# Schemtatic.net
KiCad netlist of a schematic drawn in EAGLE
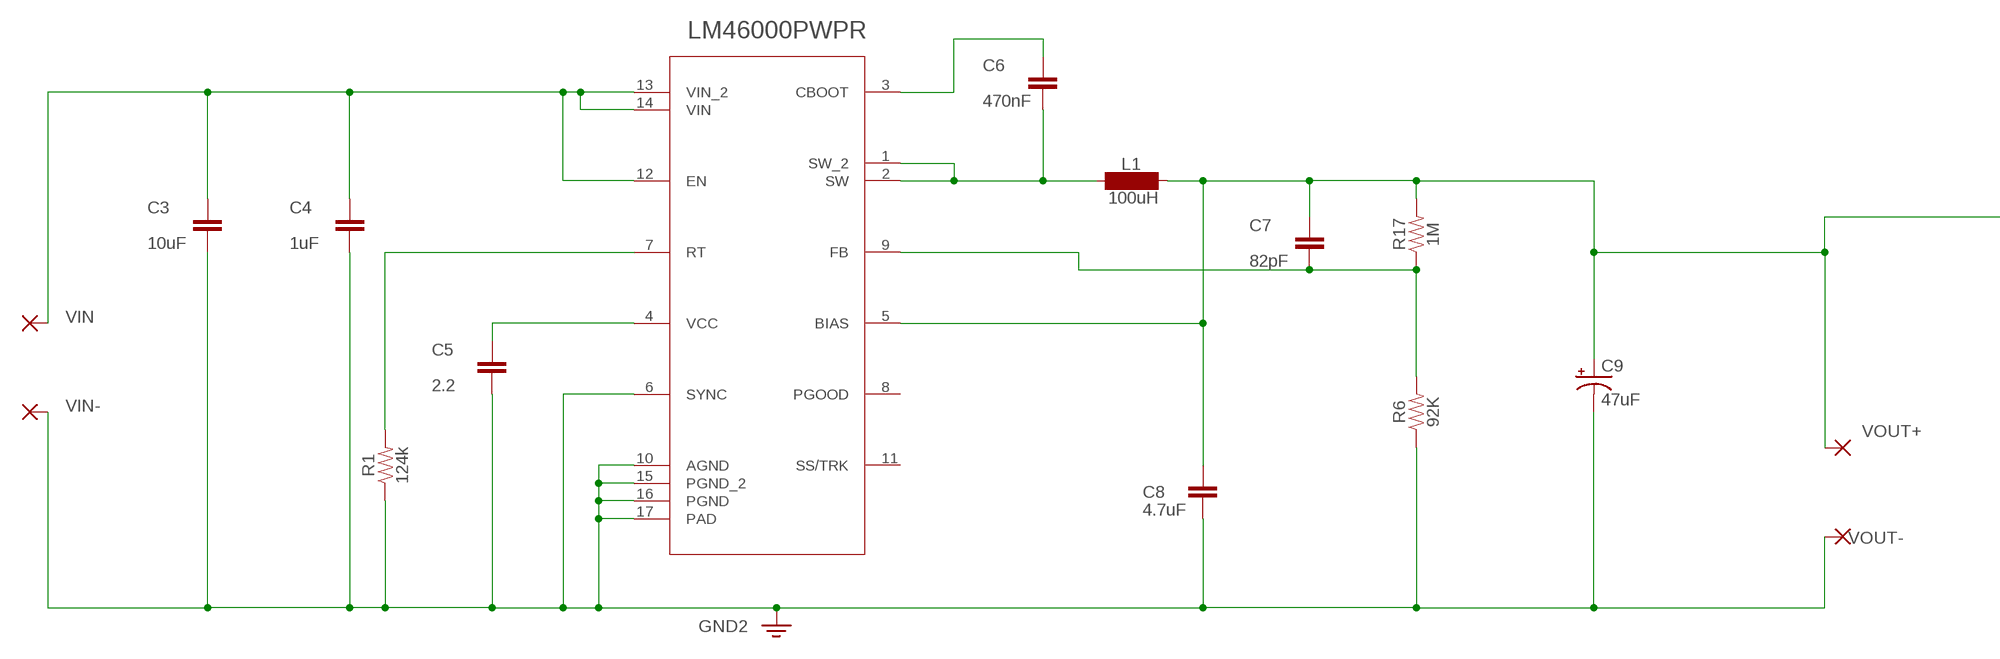
[diagram p0: schematic, sheet 1, part 1 of 2]
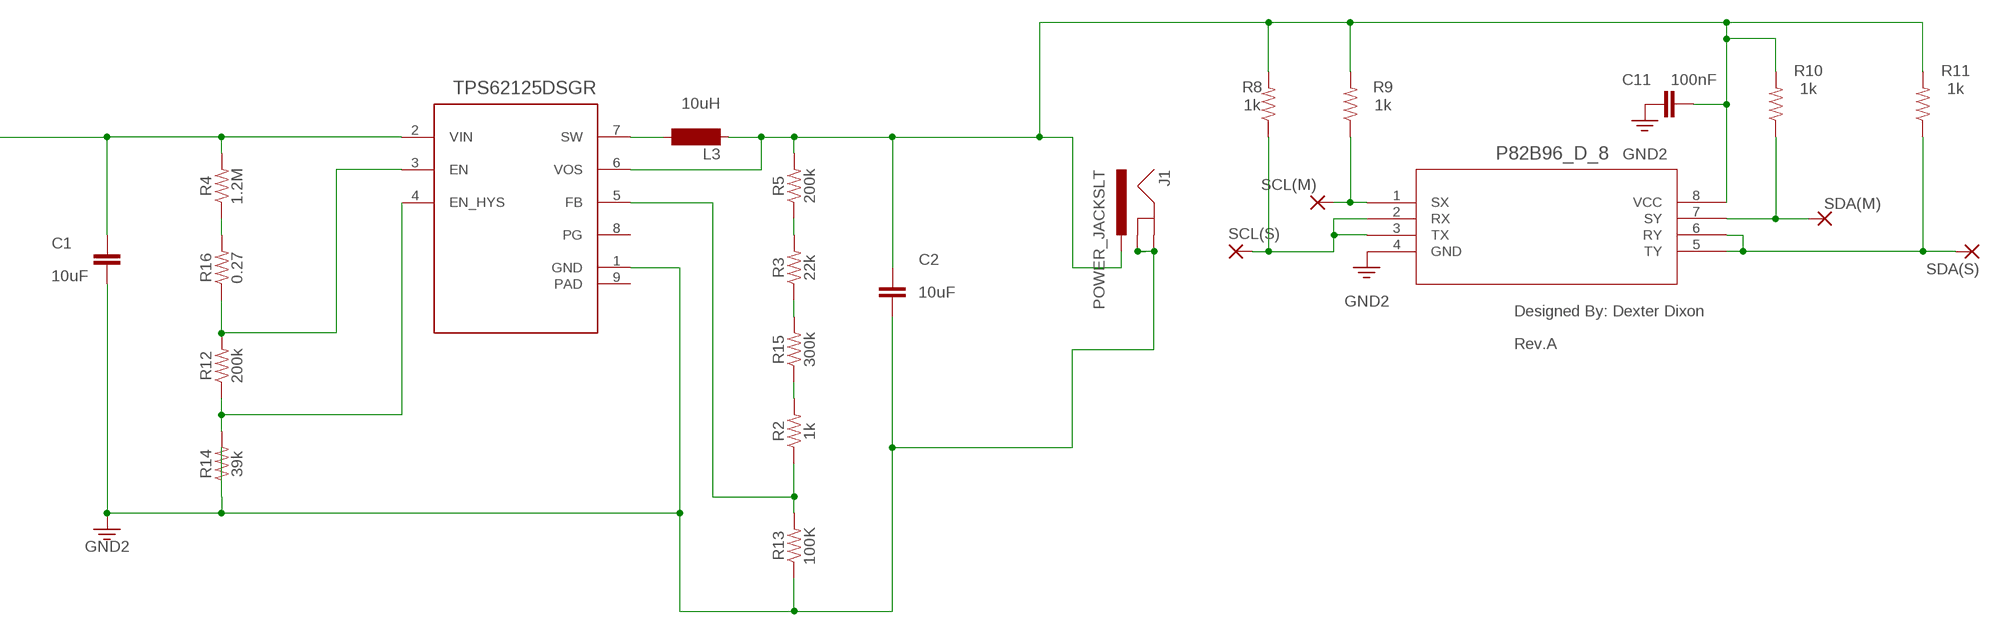
[diagram p1: schematic, sheet 1, part 2 of 2]

(export (version "E")
  (design (tool "Eeschema 10.0.6"))
  (components
    (comp (ref "C1")
      (value "10uF")
      (footprint "eagle-import:C2.5-3")
      (libsource (lib "eagle-import") (part "C2,5-3"))
    )
    (comp (ref "C2")
      (value "10uF")
      (footprint "eagle-import:C2.5-3")
      (libsource (lib "eagle-import") (part "C2,5-3"))
    )
    (comp (ref "C3")
      (value "10uF")
      (footprint "eagle-import:C2.5-3")
      (libsource (lib "eagle-import") (part "C2,5-3"))
    )
    (comp (ref "C4")
      (value "1uF")
      (footprint "eagle-import:C2.5-3")
      (libsource (lib "eagle-import") (part "C2,5-3"))
    )
    (comp (ref "C5")
      (value "2.2")
      (footprint "eagle-import:C2.5-3")
      (libsource (lib "eagle-import") (part "C2,5-3"))
    )
    (comp (ref "C6")
      (value "470nF")
      (footprint "eagle-import:C2.5-3")
      (libsource (lib "eagle-import") (part "C2,5-3"))
    )
    (comp (ref "C7")
      (value "82pF")
      (footprint "eagle-import:C2.5-3")
      (libsource (lib "eagle-import") (part "C2,5-3"))
    )
    (comp (ref "C8")
      (value "4.7uF")
      (footprint "eagle-import:C2.5-3")
      (libsource (lib "eagle-import") (part "C2,5-3"))
    )
    (comp (ref "C9")
      (value "47uF")
      (footprint "eagle-import:EIA3528")
      (libsource (lib "eagle-import") (part "47UF-POLAR-EIA3528-10V-10%"))
    )
    (comp (ref "C11")
      (value "100nF")
      (footprint "eagle-import:C2.5-3")
      (libsource (lib "eagle-import") (part "C2,5-3"))
    )
    (comp (ref "J1")
      (value "POWER_JACKSLT")
      (footprint "eagle-import:POWER_JACK_SLOT")
      (libsource (lib "eagle-import") (part "POWER_JACKSLT"))
    )
    (comp (ref "L1")
      (value "100uH")
      (footprint "eagle-import:MS42")
      (libsource (lib "eagle-import") (part "MS42"))
    )
    (comp (ref "L3")
      (value "10uH")
      (footprint "eagle-import:MS42")
      (libsource (lib "eagle-import") (part "MS42"))
    )
    (comp (ref "R1")
      (value "124k")
      (footprint "eagle-import:0603")
      (libsource (lib "eagle-import") (part "100KOHM-0603-1/10W-1%"))
    )
    (comp (ref "R2")
      (value "1k")
      (footprint "eagle-import:0603")
      (libsource (lib "eagle-import") (part "1KOHM-0603-1/10W-1%"))
    )
    (comp (ref "R3")
      (value "22k")
      (footprint "eagle-import:0603")
      (libsource (lib "eagle-import") (part "22KOHM-0603-1/10W-1%"))
    )
    (comp (ref "R4")
      (value "1.2M")
      (footprint "eagle-import:0603")
      (libsource (lib "eagle-import") (part "1.2MOHM-0603-1/10W-1%"))
    )
    (comp (ref "R5")
      (value "200k")
      (footprint "eagle-import:0603")
      (libsource (lib "eagle-import") (part "200KOHM-0603-1/10W-1%"))
    )
    (comp (ref "R6")
      (value "92K")
      (footprint "eagle-import:0402")
      (libsource (lib "eagle-import") (part "100KOHM-0402-1/16W-1%"))
    )
    (comp (ref "R8")
      (value "1k")
      (footprint "eagle-import:0603")
      (libsource (lib "eagle-import") (part "1KOHM-0603-1/10W-1%"))
    )
    (comp (ref "R9")
      (value "1k")
      (footprint "eagle-import:0603")
      (libsource (lib "eagle-import") (part "1KOHM-0603-1/10W-1%"))
    )
    (comp (ref "R10")
      (value "1k")
      (footprint "eagle-import:0603")
      (libsource (lib "eagle-import") (part "1KOHM-0603-1/10W-1%"))
    )
    (comp (ref "R11")
      (value "1k")
      (footprint "eagle-import:0603")
      (libsource (lib "eagle-import") (part "1KOHM-0603-1/10W-1%"))
    )
    (comp (ref "R12")
      (value "200k")
      (footprint "eagle-import:0603")
      (libsource (lib "eagle-import") (part "200KOHM-0603-1/10W-1%"))
    )
    (comp (ref "R13")
      (value "100K")
      (footprint "eagle-import:0402")
      (libsource (lib "eagle-import") (part "100KOHM-0402-1/16W-1%"))
    )
    (comp (ref "R14")
      (value "39k")
      (footprint "eagle-import:0603")
      (libsource (lib "eagle-import") (part "39KOHM-0603-1/10W-1%"))
    )
    (comp (ref "R15")
      (value "300k")
      (footprint "eagle-import:0603")
      (libsource (lib "eagle-import") (part "300KOHM-0603-1/10W-1%"))
    )
    (comp (ref "R16")
      (value "0.27")
      (footprint "eagle-import:0603")
      (libsource (lib "eagle-import") (part "0.27OHM-0603-1/10W-1%"))
    )
    (comp (ref "R17")
      (value "1M")
      (footprint "eagle-import:0603")
      (libsource (lib "eagle-import") (part "1MOHM-0603-1/4W-5%"))
    )
    (comp (ref "SCL(M)")
      (value "SMD5")
      (footprint "eagle-import:SMD2,54-5,08")
      (libsource (lib "eagle-import") (part "SMD5"))
    )
    (comp (ref "SCL(S)")
      (value "SMD5")
      (footprint "eagle-import:SMD2,54-5,08")
      (libsource (lib "eagle-import") (part "SMD5"))
    )
    (comp (ref "SDA(M)")
      (value "SMD5")
      (footprint "eagle-import:SMD2,54-5,08")
      (libsource (lib "eagle-import") (part "SMD5"))
    )
    (comp (ref "SDA(S)")
      (value "SMD5")
      (footprint "eagle-import:SMD2,54-5,08")
      (libsource (lib "eagle-import") (part "SMD5"))
    )
    (comp (ref "TPS62125DSGR")
      (value "Value")
      (footprint "eagle-import:DSG0008A")
      (fields
        (field (name "ALTERNATEPARTNUMBER") "TPS62125DSGT")
        (field (name "MANUFACTURER") "Texas Instruments")
        (field (name "PARTNUMBER") "TPS62125DSGR")
      )
      (libsource (lib "eagle-import") (part "TPS62125DSGR"))
    )
    (comp (ref "U1")
      (value "LM46000PWPR")
      (footprint "eagle-import:PWP0016F")
      (fields
        (field (name "MANUFACTURER") "Texas Instruments")
        (field (name "PARTNUMBER") "LM46000PWP")
        (field (name "APPROVEDBY") "Not shown in title block")
        (field (name "AUTHOR") "Not shown in title block")
        (field (name "CHECKEDBY") "Not shown in title block")
        (field (name "ENGINEER") "Not shown in title block")
        (field (name "MODIFIEDDATE") "Not shown in title block")
        (field (name "PUBLISHER") "Texas Instruments")
        (field (name "SYMBOLCREATOR") "x0208326")
      )
      (libsource (lib "eagle-import") (part "LM46000PWPR"))
    )
    (comp (ref "U2")
      (value "P82B96_D_8")
      (footprint "eagle-import:D8")
      (fields
        (field (name "GENERIC_PART_NUMBER") "P82B96")
        (field (name "MANUFACTURER") "Texas Instruments")
        (field (name "MANUFACTURER_PART_NUMBER") "p82b96_d_8")
      )
      (libsource (lib "eagle-import") (part "P82B96_D_8"))
    )
    (comp (ref "VIN+")
      (value "SMD5")
      (footprint "eagle-import:SMD2,54-5,08")
      (libsource (lib "eagle-import") (part "SMD5"))
    )
    (comp (ref "VIN-")
      (value "SMD5")
      (footprint "eagle-import:SMD2,54-5,08")
      (libsource (lib "eagle-import") (part "SMD5"))
    )
    (comp (ref "VOUT+")
      (value "SMD5")
      (footprint "eagle-import:SMD2,54-5,08")
      (libsource (lib "eagle-import") (part "SMD5"))
    )
    (comp (ref "VOUT-")
      (value "SMD5")
      (footprint "eagle-import:SMD2,54-5,08")
      (libsource (lib "eagle-import") (part "SMD5"))
    )
  )
  (nets
    (net (code "1") (name "/PAD") (class "Default")
      (node (ref "TPS62125DSGR") (pin "9") (pinfunction "PAD_9") (pintype "power_in"))
    )
    (net (code "2") (name "GND2") (class "Default")
      (node (ref "C1") (pin "2") (pinfunction "2_2") (pintype "passive"))
      (node (ref "C11") (pin "1") (pinfunction "1_1") (pintype "passive"))
      (node (ref "C2") (pin "2") (pinfunction "2_2") (pintype "passive"))
      (node (ref "C3") (pin "2") (pinfunction "2_2") (pintype "passive"))
      (node (ref "C4") (pin "2") (pinfunction "2_2") (pintype "passive"))
      (node (ref "C5") (pin "2") (pinfunction "2_2") (pintype "passive"))
      (node (ref "C8") (pin "2") (pinfunction "2_2") (pintype "passive"))
      (node (ref "C9") (pin "C") (pinfunction "-_C") (pintype "passive"))
      (node (ref "J1") (pin "GND@1") (pinfunction "GNDBREAK_GND@1") (pintype "bidirectional"))
      (node (ref "J1") (pin "GND@2") (pinfunction "GND_GND@2") (pintype "bidirectional"))
      (node (ref "R1") (pin "1") (pinfunction "1_1") (pintype "passive"))
      (node (ref "R13") (pin "1") (pinfunction "1_1") (pintype "passive"))
      (node (ref "R14") (pin "1") (pinfunction "1_1") (pintype "passive"))
      (node (ref "R6") (pin "1") (pinfunction "1_1") (pintype "passive"))
      (node (ref "TPS62125DSGR") (pin "1") (pinfunction "GND_1") (pintype "power_in"))
      (node (ref "U1") (pin "10") (pinfunction "AGND_10") (pintype "power_in"))
      (node (ref "U1") (pin "15") (pinfunction "PGND_2_15") (pintype "power_in"))
      (node (ref "U1") (pin "16") (pinfunction "PGND_16") (pintype "power_in"))
      (node (ref "U1") (pin "17") (pinfunction "PAD_17") (pintype "power_in"))
      (node (ref "U1") (pin "6") (pinfunction "SYNC_6") (pintype "input"))
      (node (ref "U2") (pin "4") (pinfunction "GND_4") (pintype "power_in"))
      (node (ref "VIN-") (pin "1") (pinfunction "P_1") (pintype "passive"))
      (node (ref "VOUT-") (pin "1") (pinfunction "P_1") (pintype "passive"))
    )
    (net (code "3") (name "Net-(C9-+)") (class "Default")
      (node (ref "C1") (pin "1") (pinfunction "1_1") (pintype "passive"))
      (node (ref "C7") (pin "1") (pinfunction "1_1") (pintype "passive"))
      (node (ref "C8") (pin "1") (pinfunction "1_1") (pintype "passive"))
      (node (ref "C9") (pin "A") (pinfunction "+_A") (pintype "passive"))
      (node (ref "L1") (pin "1") (pinfunction "1_1") (pintype "passive"))
      (node (ref "R17") (pin "2") (pinfunction "2_2") (pintype "passive"))
      (node (ref "R4") (pin "2") (pinfunction "2_2") (pintype "passive"))
      (node (ref "TPS62125DSGR") (pin "2") (pinfunction "VIN_2") (pintype "power_in"))
      (node (ref "U1") (pin "5") (pinfunction "BIAS_5") (pintype "power_in"))
      (node (ref "VOUT+") (pin "1") (pinfunction "P_1") (pintype "passive"))
    )
    (net (code "4") (name "Net-(R3-Pad2)") (class "Default")
      (node (ref "R3") (pin "2") (pinfunction "2_2") (pintype "passive"))
      (node (ref "R5") (pin "1") (pinfunction "1_1") (pintype "passive"))
    )
    (net (code "5") (name "Net-(R15-Pad1)") (class "Default")
      (node (ref "R15") (pin "1") (pinfunction "1_1") (pintype "passive"))
      (node (ref "R2") (pin "2") (pinfunction "2_2") (pintype "passive"))
    )
    (net (code "6") (name "Net-(R15-Pad2)") (class "Default")
      (node (ref "R15") (pin "2") (pinfunction "2_2") (pintype "passive"))
      (node (ref "R3") (pin "1") (pinfunction "1_1") (pintype "passive"))
    )
    (net (code "7") (name "Net-(R16-Pad2)") (class "Default")
      (node (ref "R16") (pin "2") (pinfunction "2_2") (pintype "passive"))
      (node (ref "R4") (pin "1") (pinfunction "1_1") (pintype "passive"))
    )
    (net (code "8") (name "Net-(SCL(M)-P)") (class "Default")
      (node (ref "R9") (pin "1") (pinfunction "1_1") (pintype "passive"))
      (node (ref "SCL(M)") (pin "1") (pinfunction "P_1") (pintype "passive"))
      (node (ref "U2") (pin "1") (pinfunction "SX_1") (pintype "passive"))
    )
    (net (code "9") (name "Net-(SCL(S)-P)") (class "Default")
      (node (ref "R8") (pin "1") (pinfunction "1_1") (pintype "passive"))
      (node (ref "SCL(S)") (pin "1") (pinfunction "P_1") (pintype "passive"))
      (node (ref "U2") (pin "2") (pinfunction "RX_2") (pintype "passive"))
      (node (ref "U2") (pin "3") (pinfunction "TX_3") (pintype "passive"))
    )
    (net (code "10") (name "Net-(SDA(M)-P)") (class "Default")
      (node (ref "R10") (pin "1") (pinfunction "1_1") (pintype "passive"))
      (node (ref "SDA(M)") (pin "1") (pinfunction "P_1") (pintype "passive"))
      (node (ref "U2") (pin "7") (pinfunction "SY_7") (pintype "passive"))
    )
    (net (code "11") (name "Net-(SDA(S)-P)") (class "Default")
      (node (ref "R11") (pin "1") (pinfunction "1_1") (pintype "passive"))
      (node (ref "SDA(S)") (pin "1") (pinfunction "P_1") (pintype "passive"))
      (node (ref "U2") (pin "5") (pinfunction "TY_5") (pintype "passive"))
      (node (ref "U2") (pin "6") (pinfunction "RY_6") (pintype "passive"))
    )
    (net (code "12") (name "Net-(TPS62125DSGR-EN)") (class "Default")
      (node (ref "R12") (pin "2") (pinfunction "2_2") (pintype "passive"))
      (node (ref "R16") (pin "1") (pinfunction "1_1") (pintype "passive"))
      (node (ref "TPS62125DSGR") (pin "3") (pinfunction "EN_3") (pintype "input"))
    )
    (net (code "13") (name "Net-(TPS62125DSGR-EN_HYS)") (class "Default")
      (node (ref "R12") (pin "1") (pinfunction "1_1") (pintype "passive"))
      (node (ref "R14") (pin "2") (pinfunction "2_2") (pintype "passive"))
      (node (ref "TPS62125DSGR") (pin "4") (pinfunction "EN_HYS_4") (pintype "output"))
    )
    (net (code "14") (name "Net-(TPS62125DSGR-FB)") (class "Default")
      (node (ref "R13") (pin "2") (pinfunction "2_2") (pintype "passive"))
      (node (ref "R2") (pin "1") (pinfunction "1_1") (pintype "passive"))
      (node (ref "TPS62125DSGR") (pin "5") (pinfunction "FB_5") (pintype "input"))
    )
    (net (code "15") (name "Net-(TPS62125DSGR-SW)") (class "Default")
      (node (ref "L3") (pin "2") (pinfunction "2_2") (pintype "passive"))
      (node (ref "TPS62125DSGR") (pin "7") (pinfunction "SW_7") (pintype "power_in"))
    )
    (net (code "16") (name "Net-(TPS62125DSGR-VOS)") (class "Default")
      (node (ref "C11") (pin "2") (pinfunction "2_2") (pintype "passive"))
      (node (ref "C2") (pin "1") (pinfunction "1_1") (pintype "passive"))
      (node (ref "J1") (pin "PWR") (pinfunction "PWR_PWR") (pintype "bidirectional"))
      (node (ref "L3") (pin "1") (pinfunction "1_1") (pintype "passive"))
      (node (ref "R10") (pin "2") (pinfunction "2_2") (pintype "passive"))
      (node (ref "R11") (pin "2") (pinfunction "2_2") (pintype "passive"))
      (node (ref "R5") (pin "2") (pinfunction "2_2") (pintype "passive"))
      (node (ref "R8") (pin "2") (pinfunction "2_2") (pintype "passive"))
      (node (ref "R9") (pin "2") (pinfunction "2_2") (pintype "passive"))
      (node (ref "TPS62125DSGR") (pin "6") (pinfunction "VOS_6") (pintype "input"))
      (node (ref "U2") (pin "8") (pinfunction "VCC_8") (pintype "power_in"))
    )
    (net (code "17") (name "Net-(U1-CBOOT)") (class "Default")
      (node (ref "C6") (pin "1") (pinfunction "1_1") (pintype "passive"))
      (node (ref "U1") (pin "3") (pinfunction "CBOOT_3") (pintype "input"))
    )
    (net (code "18") (name "Net-(U1-EN)") (class "Default")
      (node (ref "C3") (pin "1") (pinfunction "1_1") (pintype "passive"))
      (node (ref "C4") (pin "1") (pinfunction "1_1") (pintype "passive"))
      (node (ref "U1") (pin "12") (pinfunction "EN_12") (pintype "input"))
      (node (ref "U1") (pin "13") (pinfunction "VIN_2_13") (pintype "power_in"))
      (node (ref "U1") (pin "14") (pinfunction "VIN_14") (pintype "power_in"))
      (node (ref "VIN+") (pin "1") (pinfunction "P_1") (pintype "passive"))
    )
    (net (code "19") (name "Net-(U1-FB)") (class "Default")
      (node (ref "C7") (pin "2") (pinfunction "2_2") (pintype "passive"))
      (node (ref "R17") (pin "1") (pinfunction "1_1") (pintype "passive"))
      (node (ref "R6") (pin "2") (pinfunction "2_2") (pintype "passive"))
      (node (ref "U1") (pin "9") (pinfunction "FB_9") (pintype "input"))
    )
    (net (code "20") (name "Net-(U1-RT)") (class "Default")
      (node (ref "R1") (pin "2") (pinfunction "2_2") (pintype "passive"))
      (node (ref "U1") (pin "7") (pinfunction "RT_7") (pintype "input"))
    )
    (net (code "21") (name "Net-(U1-SW)") (class "Default")
      (node (ref "C6") (pin "2") (pinfunction "2_2") (pintype "passive"))
      (node (ref "L1") (pin "2") (pinfunction "2_2") (pintype "passive"))
      (node (ref "U1") (pin "1") (pinfunction "SW_2_1") (pintype "power_in"))
      (node (ref "U1") (pin "2") (pinfunction "SW_2") (pintype "power_in"))
    )
    (net (code "22") (name "Net-(U1-VCC)") (class "Default")
      (node (ref "C5") (pin "1") (pinfunction "1_1") (pintype "passive"))
      (node (ref "U1") (pin "4") (pinfunction "VCC_4") (pintype "power_in"))
    )
    (net (code "23") (name "unconnected-(TPS62125DSGR-PG-Pad8)") (class "Default")
      (node (ref "TPS62125DSGR") (pin "8") (pinfunction "PG_8") (pintype "output"))
    )
    (net (code "24") (name "unconnected-(U1-PGOOD-Pad8)") (class "Default")
      (node (ref "U1") (pin "8") (pinfunction "PGOOD_8") (pintype "output"))
    )
    (net (code "25") (name "unconnected-(U1-SS{slash}TRK-Pad11)") (class "Default")
      (node (ref "U1") (pin "11") (pinfunction "SS/TRK_11") (pintype "input"))
    )
  )
)
